# 5V_Converter.net
KiCad netlist of a schematic drawn in Altium Designer
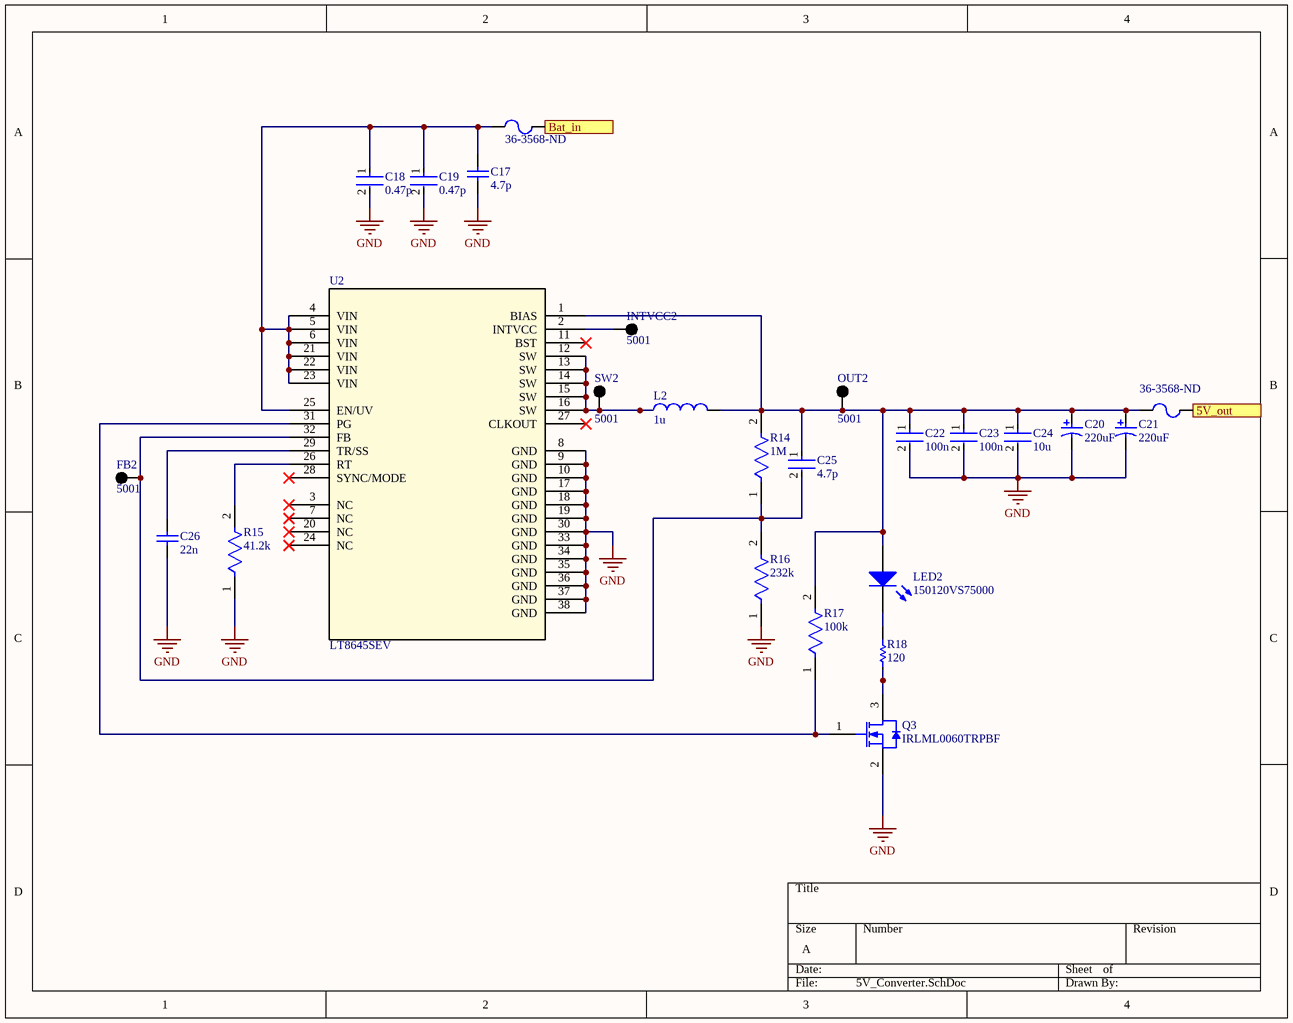
[diagram p0: 5V_Converter.SchDoc]

(export (version "E")
  (design (tool "Eeschema 10.0.6"))
  (components
    (comp (ref "C17")
      (value "4.7p")
      (footprint "CAPC1608X90X35ML10T15")
      (fields (field (name "PART NUMBER") "GRM1885C1H4R7CA01D") (field (name "MANUFACTURER") "Murata"))
      (libsource (lib "Altium Content Vault") (part "CAP"))
    )
    (comp (ref "C18")
      (value "0.47p")
      (footprint "FP-CL21-IPC_B")
      (description "CL21 Series 0805 0.47pF 50V ±0.1pF Tolerance C0G Multilayer Ceramic Chip Capacitor")
      (fields (field (name "VOLTAGE") "50V"))
      (libsource (lib "Altium Content Vault") (part "b4654b650e69147ec39a6b967a45e02"))
    )
    (comp (ref "C19")
      (value "0.47p")
      (footprint "FP-CL21-IPC_B")
      (description "CL21 Series 0805 0.47pF 50V ±0.1pF Tolerance C0G Multilayer Ceramic Chip Capacitor")
      (fields (field (name "VOLTAGE") "50V"))
      (libsource (lib "Altium Content Vault") (part "b4654b650e69147ec39a6b967a45e02"))
    )
    (comp (ref "C20")
      (value "220uF")
      (footprint "CAPPR65-500-1250X1000X1350")
      (description "Aluminum Electrolytic Capacitor, 220 uF, +/- 20%, 50 V, -40 to 85 degC, 2-Pin THD, RoHS, Bulk")
      (libsource (lib "Altium Content Vault") (part "CAP-P-2"))
    )
    (comp (ref "C21")
      (value "220uF")
      (footprint "CAPPR65-500-1250X1000X1350")
      (description "Aluminum Electrolytic Capacitor, 220 uF, +/- 20%, 50 V, -40 to 85 degC, 2-Pin THD, RoHS, Bulk")
      (libsource (lib "Altium Content Vault") (part "CAP-P-2"))
    )
    (comp (ref "C22")
      (value "100n")
      (footprint "FP-CL10-IPC_A")
      (description "Cap Ceramic 100nF 50V X7R ±10% Pad SMD 0603 +125°C T/R")
      (fields (field (name "VOLTAGE") "50V") (field (name "TOLERANCE") "10%"))
      (libsource (lib "Altium Content Vault") (part "b4654b650e69147ec39a6b967a45e02"))
    )
    (comp (ref "C23")
      (value "100n")
      (footprint "FP-CL10-IPC_A")
      (description "Cap Ceramic 100nF 50V X7R ±10% Pad SMD 0603 +125°C T/R")
      (fields (field (name "VOLTAGE") "50V") (field (name "TOLERANCE") "10%"))
      (libsource (lib "Altium Content Vault") (part "b4654b650e69147ec39a6b967a45e02"))
    )
    (comp (ref "C24")
      (value "10u")
      (footprint "FP-CGA6P-IPC_A")
      (description "Cap Ceramic 10uF 50V X7S 10% Pad SMD 1210 +125°C Automotive T/R")
      (fields (field (name "TOLERANCE") "10%") (field (name "VOLTAGE") "50V"))
      (libsource (lib "Altium Content Vault") (part "b4654b650e69147ec39a6b967a45e02"))
    )
    (comp (ref "C25")
      (value "4.7p")
      (footprint "FP-0603-L_1_6_0_15-W_0_81-MFG")
      (description "General Purpose Ceramic Capacitor, 0603, 4.7pF, 0.25pF, NP0, 30ppm/°C, 50V")
      (libsource (lib "Altium Content Vault") (part "02cd4be3c70576c341d710602a673aa"))
    )
    (comp (ref "C26")
      (value "22n")
      (footprint "CAPC1608X90X35ML10T15")
      (fields (field (name "MANUFACTURER") "Murata") (field (name "PART NUMBER") "GRM188R71H223KA01D"))
      (libsource (lib "Altium Content Vault") (part "CAP"))
    )
    (comp (ref "F3")
      (value "36-3568-ND")
      (footprint "PCBComponent_1")
      (libsource (lib "3568FuseHolder1") (part "Fuse_Holder"))
    )
    (comp (ref "F4")
      (value "36-3568-ND")
      (footprint "PCBComponent_1")
      (libsource (lib "3568FuseHolder1") (part "Fuse_Holder"))
    )
    (comp (ref "FB2")
      (value "5001")
      (footprint "KSTN-5001")
      (description "Test Point, Black, 1-Pin THD, RoHS, Bulk")
      (fields (field (name "MANUFACTURER") "Keystone"))
      (libsource (lib "Altium Content Vault") (part "KSTN-TP-5001"))
    )
    (comp (ref "INTVCC2")
      (value "5001")
      (footprint "KSTN-5001")
      (description "Test Point, Black, 1-Pin THD, RoHS, Bulk")
      (fields (field (name "MANUFACTURER") "Keystone"))
      (libsource (lib "Altium Content Vault") (part "KSTN-TP-5001"))
    )
    (comp (ref "L2")
      (value "1u")
      (footprint "PCBComponent_1")
      (libsource (lib "XAL6030-102MEC") (part "XAL6030-102MEC"))
    )
    (comp (ref "LED2")
      (value "150120VS75000")
      (footprint "1206_A")
      (description "SMD mono-color Chip LED, WL-SMCW, Bright Green")
      (fields (field (name "MANUFACTURER") "Wuerth Elektronik"))
      (libsource (lib "Altium Content Vault") (part "WE-LED_K1A2-2"))
    )
    (comp (ref "OUT2")
      (value "5001")
      (footprint "KSTN-5001")
      (description "Test Point, Black, 1-Pin THD, RoHS, Bulk")
      (fields (field (name "MANUFACTURER") "Keystone"))
      (libsource (lib "Altium Content Vault") (part "KSTN-TP-5001"))
    )
    (comp (ref "Q3")
      (value "IRLML0060TRPBF")
      (footprint "INTR-SOT-23-3_V")
      (description "HEXFET Power MOSFET\r\n, 60 V, 2.7 A, -55 to 150 degC, 3-Pin SOT-23, RoHS, Tape and Reel")
      (fields (field (name "MANUFACTURER") "International Rectifier"))
      (libsource (lib "Altium Content Vault") (part "NEMOS-GSD-3"))
    )
    (comp (ref "R14")
      (value "1M")
      (footprint "FP-CRCW0603-e3-MFG")
      (description "RES Thick Film, 1MΩ, 1%, 0.1W, 100ppm/°C, 0603")
      (fields (field (name "TOLERANCE") "1%"))
      (libsource (lib "Altium Content Vault") (part "1029c3af85768c4190bb7ad29bc67b5"))
    )
    (comp (ref "R15")
      (value "41.2k")
      (footprint "FP-CRCW0603-e3-MFG")
      (description "RES Thick Film, 41.2kΩ, 1%, 0.1W, 100ppm/°C, 0603")
      (fields (field (name "TOLERANCE") "1%"))
      (libsource (lib "Altium Content Vault") (part "1029c3af85768c4190bb7ad29bc67b5"))
    )
    (comp (ref "R16")
      (value "232k")
      (footprint "FP-CRCW0603-e3-IPC_B")
      (description "RES Thick Film, 232kΩ, 1%, 0.1W, 100ppm/°C, 0603")
      (fields (field (name "TOLERANCE") "1%"))
      (libsource (lib "Altium Content Vault") (part "1029c3af85768c4190bb7ad29bc67b5"))
    )
    (comp (ref "R17")
      (value "100k")
      (footprint "FP-RC0603-0_55-MFG")
      (description "RES SMD 100K OHM 1% 1/10W 0603")
      (fields (field (name "TOLERANCE") "1%"))
      (libsource (lib "Altium Content Vault") (part "1029c3af85768c4190bb7ad29bc67b5"))
    )
    (comp (ref "R18")
      (value "120")
      (footprint "RESC1609X55X30ML15T15")
      (description "Chip Resistor, 120 Ohm, +/- 1%, 0.1 W, -55 to 155 degC, 0603 (1608 Metric), RoHS, Tape and Reel")
      (fields (field (name "TOLERANCE") "1%") (field (name "MANUFACTURER") "Panasonic"))
      (libsource (lib "Altium Content Vault") (part "RES-2"))
    )
    (comp (ref "SW2")
      (value "5001")
      (footprint "KSTN-5001")
      (description "Test Point, Black, 1-Pin THD, RoHS, Bulk")
      (fields (field (name "MANUFACTURER") "Keystone"))
      (libsource (lib "Altium Content Vault") (part "KSTN-TP-5001"))
    )
    (comp (ref "U2")
      (value "LT8645SEV")
      (footprint "LQFN-32")
      (description "No Description Available")
      (fields (field (name "COPYRIGHT") "Copyright (C) 2018 Accelerated Designs. All rights reserved"))
      (libsource (lib "LT8645S_Library") (part "LT8645SEV"))
    )
  )
  (nets
    (net (code "1") (name "/5V_out") (class "Default")
      (node (ref "F4") (pin "2") (pinfunction "2_2") (pintype "passive"))
    )
    (net (code "2") (name "/Bat_in") (class "Default")
      (node (ref "F3") (pin "2") (pinfunction "2_2") (pintype "passive"))
    )
    (net (code "3") (name "GND") (class "Default")
      (node (ref "C17") (pin "1") (pinfunction "1_1") (pintype "passive"))
      (node (ref "C18") (pin "2") (pinfunction "2_2") (pintype "passive"))
      (node (ref "C19") (pin "2") (pinfunction "2_2") (pintype "passive"))
      (node (ref "C20") (pin "2") (pinfunction "2_2") (pintype "passive"))
      (node (ref "C21") (pin "2") (pinfunction "2_2") (pintype "passive"))
      (node (ref "C22") (pin "2") (pinfunction "2_2") (pintype "passive"))
      (node (ref "C23") (pin "2") (pinfunction "2_2") (pintype "passive"))
      (node (ref "C24") (pin "2") (pinfunction "2_2") (pintype "passive"))
      (node (ref "C26") (pin "1") (pinfunction "1_1") (pintype "passive"))
      (node (ref "Q3") (pin "2") (pinfunction "S_2") (pintype "passive"))
      (node (ref "R15") (pin "1") (pinfunction "1_1") (pintype "passive"))
      (node (ref "R16") (pin "1") (pinfunction "1_1") (pintype "passive"))
      (node (ref "U2") (pin "10") (pinfunction "GND_10") (pintype "passive"))
      (node (ref "U2") (pin "17") (pinfunction "GND_17") (pintype "passive"))
      (node (ref "U2") (pin "18") (pinfunction "GND_18") (pintype "passive"))
      (node (ref "U2") (pin "19") (pinfunction "GND_19") (pintype "passive"))
      (node (ref "U2") (pin "30") (pinfunction "GND_30") (pintype "passive"))
      (node (ref "U2") (pin "33") (pinfunction "GND_33") (pintype "passive"))
      (node (ref "U2") (pin "34") (pinfunction "GND_34") (pintype "passive"))
      (node (ref "U2") (pin "35") (pinfunction "GND_35") (pintype "passive"))
      (node (ref "U2") (pin "36") (pinfunction "GND_36") (pintype "passive"))
      (node (ref "U2") (pin "37") (pinfunction "GND_37") (pintype "passive"))
      (node (ref "U2") (pin "38") (pinfunction "GND_38") (pintype "passive"))
      (node (ref "U2") (pin "8") (pinfunction "GND_8") (pintype "passive"))
      (node (ref "U2") (pin "9") (pinfunction "GND_9") (pintype "passive"))
    )
    (net (code "4") (name "Net-(L2-Pad1)") (class "Default")
      (node (ref "L2") (pin "1") (pinfunction "1_1") (pintype "passive"))
      (node (ref "SW2") (pin "1") (pintype "passive"))
      (node (ref "U2") (pin "12") (pinfunction "SW_12") (pintype "passive"))
      (node (ref "U2") (pin "13") (pinfunction "SW_13") (pintype "passive"))
      (node (ref "U2") (pin "14") (pinfunction "SW_14") (pintype "passive"))
      (node (ref "U2") (pin "15") (pinfunction "SW_15") (pintype "passive"))
      (node (ref "U2") (pin "16") (pinfunction "SW_16") (pintype "passive"))
    )
    (net (code "5") (name "Net-(LED2-A)") (class "Default")
      (node (ref "C20") (pin "1") (pinfunction "1_1") (pintype "passive"))
      (node (ref "C21") (pin "1") (pinfunction "1_1") (pintype "passive"))
      (node (ref "C22") (pin "1") (pinfunction "1_1") (pintype "passive"))
      (node (ref "C23") (pin "1") (pinfunction "1_1") (pintype "passive"))
      (node (ref "C24") (pin "1") (pinfunction "1_1") (pintype "passive"))
      (node (ref "C25") (pin "1") (pinfunction "1_1") (pintype "passive"))
      (node (ref "F4") (pin "1") (pinfunction "1_1") (pintype "passive"))
      (node (ref "L2") (pin "2") (pinfunction "2_2") (pintype "passive"))
      (node (ref "LED2") (pin "2") (pinfunction "A_2") (pintype "passive"))
      (node (ref "OUT2") (pin "1") (pintype "passive"))
      (node (ref "R14") (pin "2") (pinfunction "2_2") (pintype "passive"))
      (node (ref "R17") (pin "2") (pinfunction "2_2") (pintype "passive"))
      (node (ref "U2") (pin "1") (pinfunction "BIAS_1") (pintype "passive"))
    )
    (net (code "6") (name "Net-(LED2-K)") (class "Default")
      (node (ref "LED2") (pin "1") (pinfunction "K_1") (pintype "passive"))
      (node (ref "R18") (pin "2") (pinfunction "2_2") (pintype "passive"))
    )
    (net (code "7") (name "Net-(Q3-D)") (class "Default")
      (node (ref "Q3") (pin "3") (pinfunction "D_3") (pintype "passive"))
      (node (ref "R18") (pin "1") (pinfunction "1_1") (pintype "passive"))
    )
    (net (code "8") (name "Net-(Q3-G)") (class "Default")
      (node (ref "Q3") (pin "1") (pinfunction "G_1") (pintype "passive"))
      (node (ref "R17") (pin "1") (pinfunction "1_1") (pintype "passive"))
      (node (ref "U2") (pin "31") (pinfunction "PG_31") (pintype "passive"))
    )
    (net (code "9") (name "Net-(U2-EN{slash}UV)") (class "Default")
      (node (ref "C17") (pin "2") (pinfunction "2_2") (pintype "passive"))
      (node (ref "C18") (pin "1") (pinfunction "1_1") (pintype "passive"))
      (node (ref "C19") (pin "1") (pinfunction "1_1") (pintype "passive"))
      (node (ref "F3") (pin "1") (pinfunction "1_1") (pintype "passive"))
      (node (ref "U2") (pin "21") (pinfunction "VIN_21") (pintype "passive"))
      (node (ref "U2") (pin "22") (pinfunction "VIN_22") (pintype "passive"))
      (node (ref "U2") (pin "23") (pinfunction "VIN_23") (pintype "passive"))
      (node (ref "U2") (pin "25") (pinfunction "EN/UV_25") (pintype "passive"))
      (node (ref "U2") (pin "4") (pinfunction "VIN_4") (pintype "passive"))
      (node (ref "U2") (pin "5") (pinfunction "VIN_5") (pintype "passive"))
      (node (ref "U2") (pin "6") (pinfunction "VIN_6") (pintype "passive"))
    )
    (net (code "10") (name "Net-(U2-FB)") (class "Default")
      (node (ref "C25") (pin "2") (pinfunction "2_2") (pintype "passive"))
      (node (ref "FB2") (pin "1") (pintype "passive"))
      (node (ref "R14") (pin "1") (pinfunction "1_1") (pintype "passive"))
      (node (ref "R16") (pin "2") (pinfunction "2_2") (pintype "passive"))
      (node (ref "U2") (pin "32") (pinfunction "FB_32") (pintype "passive"))
    )
    (net (code "11") (name "Net-(U2-INTVCC)") (class "Default")
      (node (ref "INTVCC2") (pin "1") (pintype "passive"))
      (node (ref "U2") (pin "2") (pinfunction "INTVCC_2") (pintype "passive"))
    )
    (net (code "12") (name "Net-(U2-RT)") (class "Default")
      (node (ref "R15") (pin "2") (pinfunction "2_2") (pintype "passive"))
      (node (ref "U2") (pin "26") (pinfunction "RT_26") (pintype "passive"))
    )
    (net (code "13") (name "Net-(U2-TR{slash}SS)") (class "Default")
      (node (ref "C26") (pin "2") (pinfunction "2_2") (pintype "passive"))
      (node (ref "U2") (pin "29") (pinfunction "TR/SS_29") (pintype "passive"))
    )
    (net (code "14") (name "unconnected-(U2-BST-Pad11)") (class "Default")
      (node (ref "U2") (pin "11") (pinfunction "BST_11") (pintype "passive+no_connect"))
    )
    (net (code "15") (name "unconnected-(U2-CLKOUT-Pad27)") (class "Default")
      (node (ref "U2") (pin "27") (pinfunction "CLKOUT_27") (pintype "passive+no_connect"))
    )
    (net (code "16") (name "unconnected-(U2-NC-Pad3)") (class "Default")
      (node (ref "U2") (pin "3") (pinfunction "NC_3") (pintype "passive+no_connect"))
    )
    (net (code "17") (name "unconnected-(U2-NC-Pad7)") (class "Default")
      (node (ref "U2") (pin "7") (pinfunction "NC_7") (pintype "passive+no_connect"))
    )
    (net (code "18") (name "unconnected-(U2-NC-Pad20)") (class "Default")
      (node (ref "U2") (pin "20") (pinfunction "NC_20") (pintype "passive+no_connect"))
    )
    (net (code "19") (name "unconnected-(U2-NC-Pad24)") (class "Default")
      (node (ref "U2") (pin "24") (pinfunction "NC_24") (pintype "passive+no_connect"))
    )
    (net (code "20") (name "unconnected-(U2-SYNC{slash}MODE-Pad28)") (class "Default")
      (node (ref "U2") (pin "28") (pinfunction "SYNC/MODE_28") (pintype "passive+no_connect"))
    )
  )
)
